# Adapter_JLink.net
KiCad netlist of a schematic drawn in Altium Designer
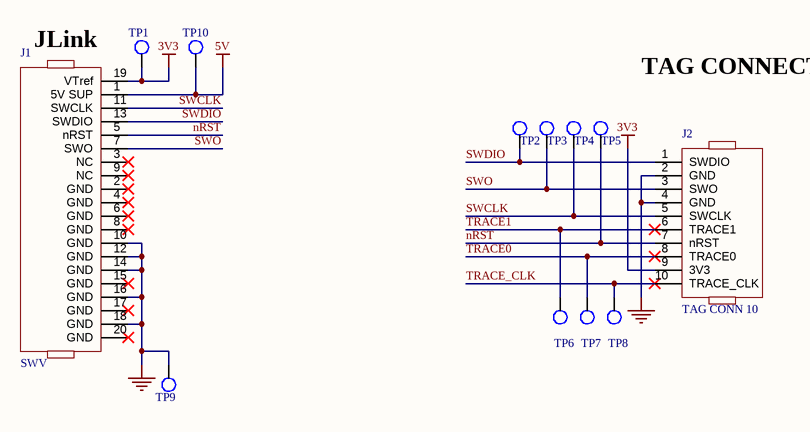
[diagram p0: Adapter_JLink.SchDoc]

(export (version "E")
  (design (tool "Eeschema 10.0.6"))
  (components
    (comp (ref "J1")
      (value "SWV")
      (footprint "CONN HDR PLUG 20 2.54 TH STLINKV2")
      (description "Female, 20C, Straight .100\"CC; No Mt. w/Center Polarizing Key; PBT, Brass, Gold Flash, 105 C")
      (fields
        (field (name "MANUFACTURER") "Sullins")
        (field (name "MANUFACTURER PART NUMBER") "SFH11-PBPC-D10-ST-BK")
      )
      (libsource (lib "Symbols") (part "CONN HDR PLUG 20 2.54mm TH JLINK"))
    )
    (comp (ref "J2")
      (value "TAG CONN 10")
      (footprint "CONN HDR RECPT 10 2.54 TH TAG CONNECT")
      (description "Conn Shrouded Header HDR 10 POS 2.54mm Solder ST Thru-Hole")
      (fields
        (field (name "MANUFACTURER") "On-Shore Technology")
        (field (name "MANUFACTURER PART NUMBER") "302-S101")
      )
      (libsource (lib "Symbols") (part "CONN HDR RECPT 10 2.54mm TH SWV"))
    )
    (comp (ref "TP1")
      (value "1mm")
      (footprint "TESTPOINT_SMT")
      (description "SMT testpoint")
      (libsource (lib "Adapter_SchematicLib") (part "TP 1mm"))
    )
    (comp (ref "TP2")
      (value "1mm")
      (footprint "TESTPOINT_SMT")
      (description "SMT testpoint")
      (libsource (lib "Adapter_SchematicLib") (part "TP 1mm"))
    )
    (comp (ref "TP3")
      (value "1mm")
      (footprint "TESTPOINT_SMT")
      (description "SMT testpoint")
      (libsource (lib "Adapter_SchematicLib") (part "TP 1mm"))
    )
    (comp (ref "TP4")
      (value "1mm")
      (footprint "TESTPOINT_SMT")
      (description "SMT testpoint")
      (libsource (lib "Adapter_SchematicLib") (part "TP 1mm"))
    )
    (comp (ref "TP5")
      (value "1mm")
      (footprint "TESTPOINT_SMT")
      (description "SMT testpoint")
      (libsource (lib "Adapter_SchematicLib") (part "TP 1mm"))
    )
    (comp (ref "TP6")
      (value "1mm")
      (footprint "TESTPOINT_SMT")
      (description "SMT testpoint")
      (libsource (lib "Adapter_SchematicLib") (part "TP 1mm"))
    )
    (comp (ref "TP7")
      (value "1mm")
      (footprint "TESTPOINT_SMT")
      (description "SMT testpoint")
      (libsource (lib "Adapter_SchematicLib") (part "TP 1mm"))
    )
    (comp (ref "TP8")
      (value "1mm")
      (footprint "TESTPOINT_SMT")
      (description "SMT testpoint")
      (libsource (lib "Adapter_SchematicLib") (part "TP 1mm"))
    )
    (comp (ref "TP9")
      (value "1mm")
      (footprint "TESTPOINT_SMT")
      (description "SMT testpoint")
      (libsource (lib "Adapter_SchematicLib") (part "TP 1mm"))
    )
    (comp (ref "TP10")
      (value "1mm")
      (footprint "TESTPOINT_SMT")
      (description "SMT testpoint")
      (libsource (lib "Adapter_SchematicLib") (part "TP 1mm"))
    )
  )
  (nets
    (net (code "1") (name "/SWCLK") (class "Default")
      (node (ref "J1") (pin "11") (pinfunction "SWCLK_11") (pintype "passive"))
      (node (ref "J2") (pin "5") (pinfunction "SWCLK_5") (pintype "passive"))
      (node (ref "TP4") (pin "1") (pinfunction "1_1") (pintype "passive"))
    )
    (net (code "2") (name "/SWDIO") (class "Default")
      (node (ref "J1") (pin "13") (pinfunction "SWDIO_13") (pintype "passive"))
      (node (ref "J2") (pin "1") (pinfunction "SWDIO_1") (pintype "passive"))
      (node (ref "TP2") (pin "1") (pinfunction "1_1") (pintype "passive"))
    )
    (net (code "3") (name "/SWO") (class "Default")
      (node (ref "J1") (pin "7") (pinfunction "SWO_7") (pintype "passive"))
      (node (ref "J2") (pin "3") (pinfunction "SWO_3") (pintype "passive"))
      (node (ref "TP3") (pin "1") (pinfunction "1_1") (pintype "passive"))
    )
    (net (code "4") (name "/TRACE0") (class "Default")
      (node (ref "J2") (pin "8") (pinfunction "TRACE0_8") (pintype "passive"))
      (node (ref "TP7") (pin "1") (pinfunction "1_1") (pintype "passive"))
    )
    (net (code "5") (name "/TRACE1") (class "Default")
      (node (ref "J2") (pin "6") (pinfunction "TRACE1_6") (pintype "passive"))
      (node (ref "TP6") (pin "1") (pinfunction "1_1") (pintype "passive"))
    )
    (net (code "6") (name "/TRACE_CLK") (class "Default")
      (node (ref "J2") (pin "10") (pinfunction "TRACE_CLK_10") (pintype "passive"))
      (node (ref "TP8") (pin "1") (pinfunction "1_1") (pintype "passive"))
    )
    (net (code "7") (name "/nRST") (class "Default")
      (node (ref "J1") (pin "5") (pinfunction "nRST_5") (pintype "passive"))
      (node (ref "J2") (pin "7") (pinfunction "nRST_7") (pintype "passive"))
      (node (ref "TP5") (pin "1") (pinfunction "1_1") (pintype "passive"))
    )
    (net (code "8") (name "3V3") (class "Default")
      (node (ref "J1") (pin "19") (pinfunction "VTref_19") (pintype "passive"))
      (node (ref "J2") (pin "9") (pinfunction "3V3_9") (pintype "passive"))
      (node (ref "TP1") (pin "1") (pinfunction "1_1") (pintype "passive"))
    )
    (net (code "9") (name "5V") (class "Default")
      (node (ref "J1") (pin "1") (pinfunction "5V_SUP_1") (pintype "passive"))
      (node (ref "TP10") (pin "1") (pinfunction "1_1") (pintype "passive"))
    )
    (net (code "10") (name "GND") (class "Default")
      (node (ref "J1") (pin "10") (pinfunction "GND_10") (pintype "passive"))
      (node (ref "J1") (pin "12") (pinfunction "GND_12") (pintype "passive"))
      (node (ref "J1") (pin "14") (pinfunction "GND_14") (pintype "passive"))
      (node (ref "J1") (pin "16") (pinfunction "GND_16") (pintype "passive"))
      (node (ref "J1") (pin "18") (pinfunction "GND_18") (pintype "passive"))
      (node (ref "J2") (pin "2") (pinfunction "GND_2") (pintype "passive"))
      (node (ref "J2") (pin "4") (pinfunction "GND_4") (pintype "passive"))
      (node (ref "TP9") (pin "1") (pinfunction "1_1") (pintype "passive"))
    )
    (net (code "11") (name "unconnected-(J1-GND-Pad2)") (class "Default")
      (node (ref "J1") (pin "2") (pinfunction "GND_2") (pintype "passive+no_connect"))
    )
    (net (code "12") (name "unconnected-(J1-GND-Pad4)") (class "Default")
      (node (ref "J1") (pin "4") (pinfunction "GND_4") (pintype "passive+no_connect"))
    )
    (net (code "13") (name "unconnected-(J1-GND-Pad6)") (class "Default")
      (node (ref "J1") (pin "6") (pinfunction "GND_6") (pintype "passive+no_connect"))
    )
    (net (code "14") (name "unconnected-(J1-GND-Pad8)") (class "Default")
      (node (ref "J1") (pin "8") (pinfunction "GND_8") (pintype "passive+no_connect"))
    )
    (net (code "15") (name "unconnected-(J1-GND-Pad15)") (class "Default")
      (node (ref "J1") (pin "15") (pinfunction "GND_15") (pintype "passive+no_connect"))
    )
    (net (code "16") (name "unconnected-(J1-GND-Pad17)") (class "Default")
      (node (ref "J1") (pin "17") (pinfunction "GND_17") (pintype "passive+no_connect"))
    )
    (net (code "17") (name "unconnected-(J1-GND-Pad20)") (class "Default")
      (node (ref "J1") (pin "20") (pinfunction "GND_20") (pintype "passive+no_connect"))
    )
    (net (code "18") (name "unconnected-(J1-NC-Pad3)") (class "Default")
      (node (ref "J1") (pin "3") (pinfunction "NC_3") (pintype "passive+no_connect"))
    )
    (net (code "19") (name "unconnected-(J1-NC-Pad9)") (class "Default")
      (node (ref "J1") (pin "9") (pinfunction "NC_9") (pintype "passive+no_connect"))
    )
  )
)
